# 16bit_EPROM.net
KiCad netlist of a schematic drawn in EAGLE
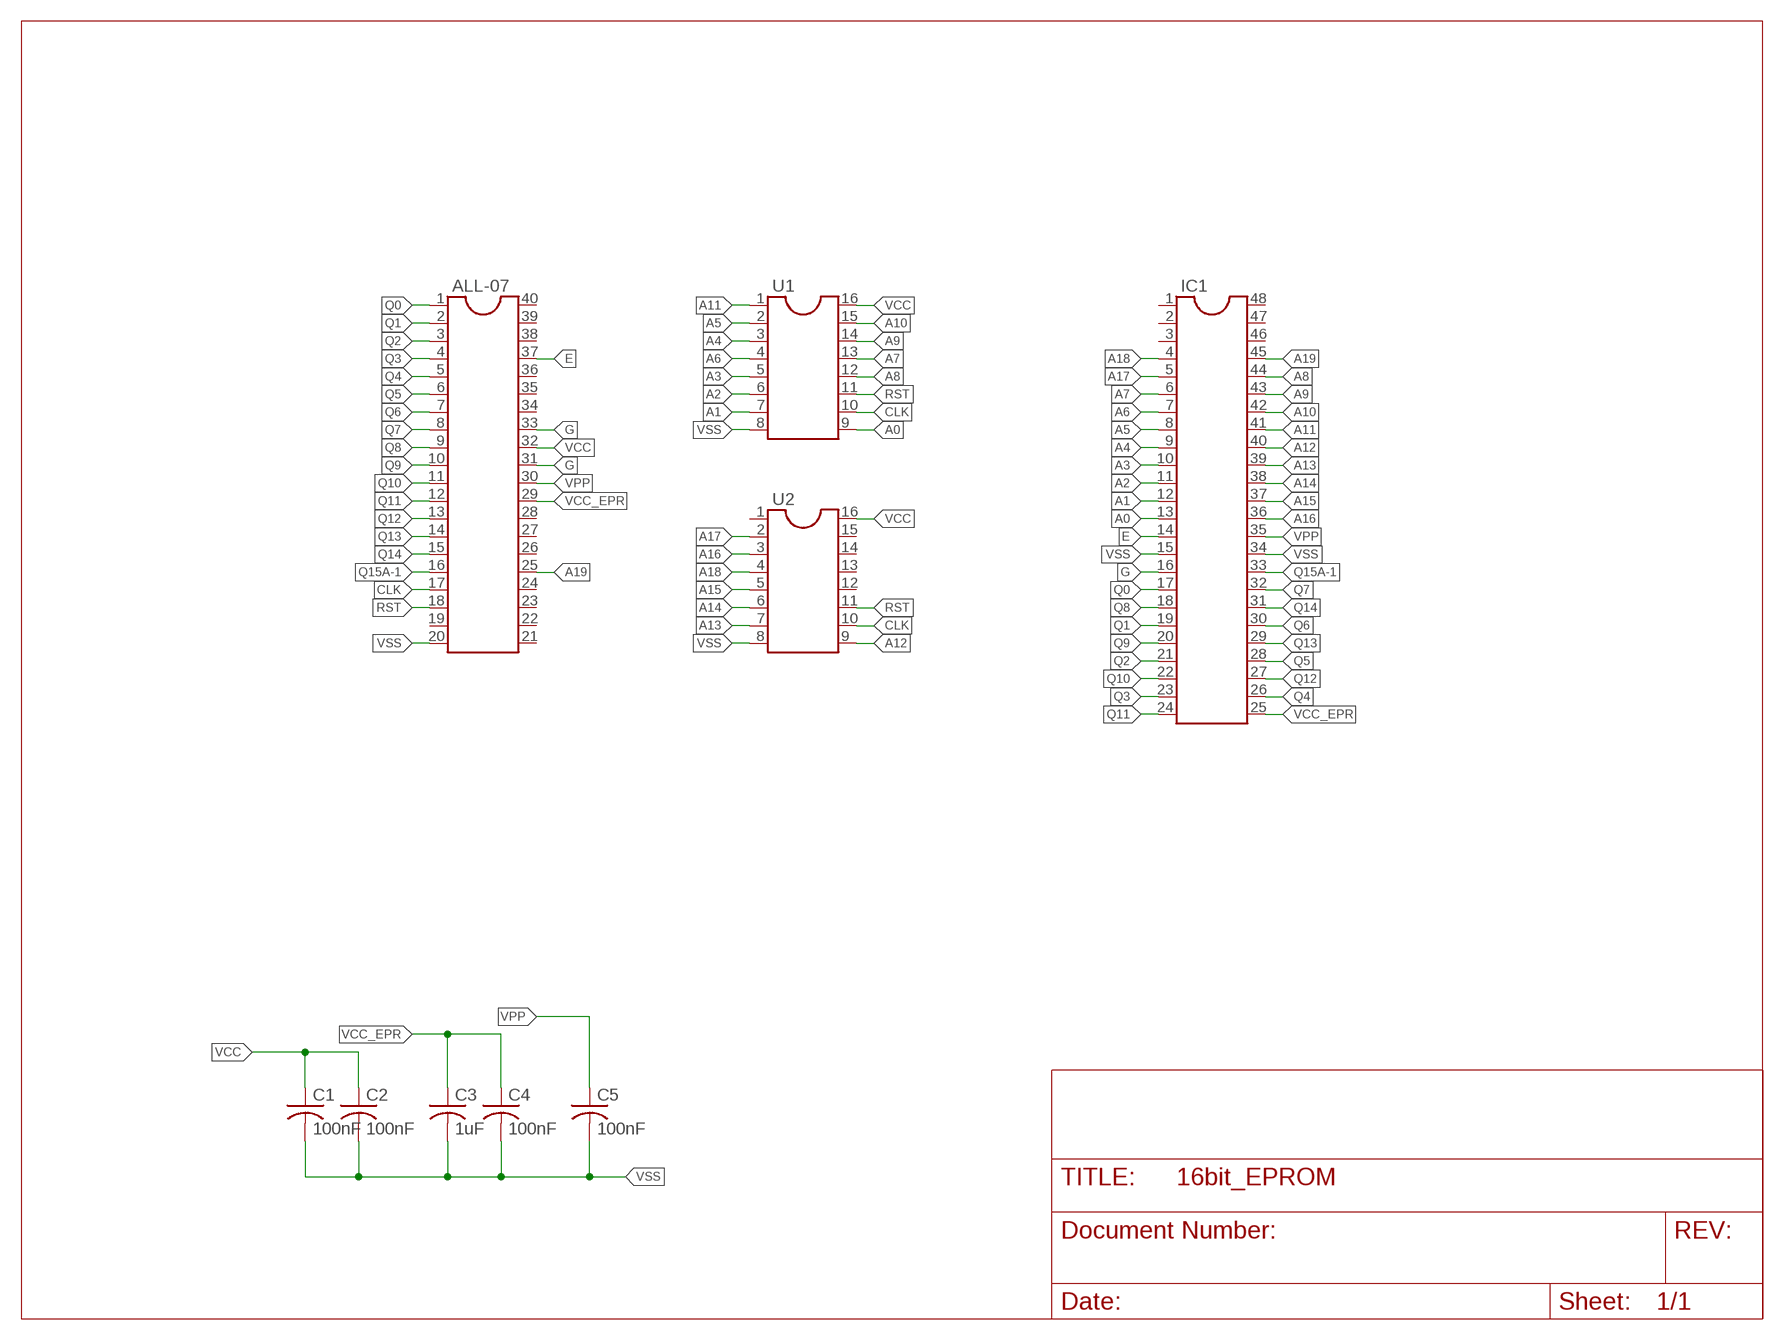
[diagram p0: schematic, sheet 1]

(export (version "E")
  (design (tool "Eeschema 10.0.6"))
  (components
    (comp (ref "ALL-07")
      (value "DIL40")
      (footprint "eagle-import:DIL40")
      (libsource (lib "eagle-import") (part "DIL40"))
    )
    (comp (ref "C1")
      (value "100nF")
      (footprint "eagle-import:C050-025X075")
      (libsource (lib "eagle-import") (part "C-US050-025X075"))
    )
    (comp (ref "C2")
      (value "100nF")
      (footprint "eagle-import:C050-025X075")
      (libsource (lib "eagle-import") (part "C-US050-025X075"))
    )
    (comp (ref "C3")
      (value "1uF")
      (footprint "eagle-import:C050-025X075")
      (libsource (lib "eagle-import") (part "C-US050-025X075"))
    )
    (comp (ref "C4")
      (value "100nF")
      (footprint "eagle-import:C050-025X075")
      (libsource (lib "eagle-import") (part "C-US050-025X075"))
    )
    (comp (ref "C5")
      (value "100nF")
      (footprint "eagle-import:C050-025X075")
      (libsource (lib "eagle-import") (part "C-US050-025X075"))
    )
    (comp (ref "IC1")
      (value "DIL48")
      (footprint "eagle-import:DIL48")
      (libsource (lib "eagle-import") (part "DIL48"))
    )
    (comp (ref "U1")
      (value "DIL16")
      (footprint "eagle-import:DIL16")
      (libsource (lib "eagle-import") (part "DIL16"))
    )
    (comp (ref "U2")
      (value "DIL16")
      (footprint "eagle-import:DIL16")
      (libsource (lib "eagle-import") (part "DIL16"))
    )
  )
  (nets
    (net (code "1") (name "A0") (class "Default")
      (node (ref "IC1") (pin "13") (pinfunction "13_13") (pintype "passive"))
      (node (ref "U1") (pin "9") (pinfunction "9_9") (pintype "passive"))
    )
    (net (code "2") (name "A1") (class "Default")
      (node (ref "IC1") (pin "12") (pinfunction "12_12") (pintype "passive"))
      (node (ref "U1") (pin "7") (pinfunction "7_7") (pintype "passive"))
    )
    (net (code "3") (name "A2") (class "Default")
      (node (ref "IC1") (pin "11") (pinfunction "11_11") (pintype "passive"))
      (node (ref "U1") (pin "6") (pinfunction "6_6") (pintype "passive"))
    )
    (net (code "4") (name "A3") (class "Default")
      (node (ref "IC1") (pin "10") (pinfunction "10_10") (pintype "passive"))
      (node (ref "U1") (pin "5") (pinfunction "5_5") (pintype "passive"))
    )
    (net (code "5") (name "A4") (class "Default")
      (node (ref "IC1") (pin "9") (pinfunction "9_9") (pintype "passive"))
      (node (ref "U1") (pin "3") (pinfunction "3_3") (pintype "passive"))
    )
    (net (code "6") (name "A5") (class "Default")
      (node (ref "IC1") (pin "8") (pinfunction "8_8") (pintype "passive"))
      (node (ref "U1") (pin "2") (pinfunction "2_2") (pintype "passive"))
    )
    (net (code "7") (name "A6") (class "Default")
      (node (ref "IC1") (pin "7") (pinfunction "7_7") (pintype "passive"))
      (node (ref "U1") (pin "4") (pinfunction "4_4") (pintype "passive"))
    )
    (net (code "8") (name "A7") (class "Default")
      (node (ref "IC1") (pin "6") (pinfunction "6_6") (pintype "passive"))
      (node (ref "U1") (pin "13") (pinfunction "13_13") (pintype "passive"))
    )
    (net (code "9") (name "A8") (class "Default")
      (node (ref "IC1") (pin "44") (pinfunction "44_44") (pintype "passive"))
      (node (ref "U1") (pin "12") (pinfunction "12_12") (pintype "passive"))
    )
    (net (code "10") (name "A9") (class "Default")
      (node (ref "IC1") (pin "43") (pinfunction "43_43") (pintype "passive"))
      (node (ref "U1") (pin "14") (pinfunction "14_14") (pintype "passive"))
    )
    (net (code "11") (name "A10") (class "Default")
      (node (ref "IC1") (pin "42") (pinfunction "42_42") (pintype "passive"))
      (node (ref "U1") (pin "15") (pinfunction "15_15") (pintype "passive"))
    )
    (net (code "12") (name "A11") (class "Default")
      (node (ref "IC1") (pin "41") (pinfunction "41_41") (pintype "passive"))
      (node (ref "U1") (pin "1") (pinfunction "1_1") (pintype "passive"))
    )
    (net (code "13") (name "A12") (class "Default")
      (node (ref "IC1") (pin "40") (pinfunction "40_40") (pintype "passive"))
      (node (ref "U2") (pin "9") (pinfunction "9_9") (pintype "passive"))
    )
    (net (code "14") (name "A13") (class "Default")
      (node (ref "IC1") (pin "39") (pinfunction "39_39") (pintype "passive"))
      (node (ref "U2") (pin "7") (pinfunction "7_7") (pintype "passive"))
    )
    (net (code "15") (name "A14") (class "Default")
      (node (ref "IC1") (pin "38") (pinfunction "38_38") (pintype "passive"))
      (node (ref "U2") (pin "6") (pinfunction "6_6") (pintype "passive"))
    )
    (net (code "16") (name "A15") (class "Default")
      (node (ref "IC1") (pin "37") (pinfunction "37_37") (pintype "passive"))
      (node (ref "U2") (pin "5") (pinfunction "5_5") (pintype "passive"))
    )
    (net (code "17") (name "A16") (class "Default")
      (node (ref "IC1") (pin "36") (pinfunction "36_36") (pintype "passive"))
      (node (ref "U2") (pin "3") (pinfunction "3_3") (pintype "passive"))
    )
    (net (code "18") (name "A17") (class "Default")
      (node (ref "IC1") (pin "5") (pinfunction "5_5") (pintype "passive"))
      (node (ref "U2") (pin "2") (pinfunction "2_2") (pintype "passive"))
    )
    (net (code "19") (name "A18") (class "Default")
      (node (ref "IC1") (pin "4") (pinfunction "4_4") (pintype "passive"))
      (node (ref "U2") (pin "4") (pinfunction "4_4") (pintype "passive"))
    )
    (net (code "20") (name "A19") (class "Default")
      (node (ref "ALL-07") (pin "25") (pinfunction "25_25") (pintype "passive"))
      (node (ref "IC1") (pin "45") (pinfunction "45_45") (pintype "passive"))
    )
    (net (code "21") (name "CLK") (class "Default")
      (node (ref "ALL-07") (pin "17") (pinfunction "17_17") (pintype "passive"))
      (node (ref "U1") (pin "10") (pinfunction "10_10") (pintype "passive"))
      (node (ref "U2") (pin "10") (pinfunction "10_10") (pintype "passive"))
    )
    (net (code "22") (name "E") (class "Default")
      (node (ref "ALL-07") (pin "37") (pinfunction "37_37") (pintype "passive"))
      (node (ref "IC1") (pin "14") (pinfunction "14_14") (pintype "passive"))
    )
    (net (code "23") (name "G") (class "Default")
      (node (ref "ALL-07") (pin "31") (pinfunction "31_31") (pintype "passive"))
      (node (ref "ALL-07") (pin "33") (pinfunction "33_33") (pintype "passive"))
      (node (ref "IC1") (pin "16") (pinfunction "16_16") (pintype "passive"))
    )
    (net (code "24") (name "Q0") (class "Default")
      (node (ref "ALL-07") (pin "1") (pinfunction "1_1") (pintype "passive"))
      (node (ref "IC1") (pin "17") (pinfunction "17_17") (pintype "passive"))
    )
    (net (code "25") (name "Q1") (class "Default")
      (node (ref "ALL-07") (pin "2") (pinfunction "2_2") (pintype "passive"))
      (node (ref "IC1") (pin "19") (pinfunction "19_19") (pintype "passive"))
    )
    (net (code "26") (name "Q2") (class "Default")
      (node (ref "ALL-07") (pin "3") (pinfunction "3_3") (pintype "passive"))
      (node (ref "IC1") (pin "21") (pinfunction "21_21") (pintype "passive"))
    )
    (net (code "27") (name "Q3") (class "Default")
      (node (ref "ALL-07") (pin "4") (pinfunction "4_4") (pintype "passive"))
      (node (ref "IC1") (pin "23") (pinfunction "23_23") (pintype "passive"))
    )
    (net (code "28") (name "Q4") (class "Default")
      (node (ref "ALL-07") (pin "5") (pinfunction "5_5") (pintype "passive"))
      (node (ref "IC1") (pin "26") (pinfunction "26_26") (pintype "passive"))
    )
    (net (code "29") (name "Q5") (class "Default")
      (node (ref "ALL-07") (pin "6") (pinfunction "6_6") (pintype "passive"))
      (node (ref "IC1") (pin "28") (pinfunction "28_28") (pintype "passive"))
    )
    (net (code "30") (name "Q6") (class "Default")
      (node (ref "ALL-07") (pin "7") (pinfunction "7_7") (pintype "passive"))
      (node (ref "IC1") (pin "30") (pinfunction "30_30") (pintype "passive"))
    )
    (net (code "31") (name "Q7") (class "Default")
      (node (ref "ALL-07") (pin "8") (pinfunction "8_8") (pintype "passive"))
      (node (ref "IC1") (pin "32") (pinfunction "32_32") (pintype "passive"))
    )
    (net (code "32") (name "Q8") (class "Default")
      (node (ref "ALL-07") (pin "9") (pinfunction "9_9") (pintype "passive"))
      (node (ref "IC1") (pin "18") (pinfunction "18_18") (pintype "passive"))
    )
    (net (code "33") (name "Q9") (class "Default")
      (node (ref "ALL-07") (pin "10") (pinfunction "10_10") (pintype "passive"))
      (node (ref "IC1") (pin "20") (pinfunction "20_20") (pintype "passive"))
    )
    (net (code "34") (name "Q10") (class "Default")
      (node (ref "ALL-07") (pin "11") (pinfunction "11_11") (pintype "passive"))
      (node (ref "IC1") (pin "22") (pinfunction "22_22") (pintype "passive"))
    )
    (net (code "35") (name "Q11") (class "Default")
      (node (ref "ALL-07") (pin "12") (pinfunction "12_12") (pintype "passive"))
      (node (ref "IC1") (pin "24") (pinfunction "24_24") (pintype "passive"))
    )
    (net (code "36") (name "Q12") (class "Default")
      (node (ref "ALL-07") (pin "13") (pinfunction "13_13") (pintype "passive"))
      (node (ref "IC1") (pin "27") (pinfunction "27_27") (pintype "passive"))
    )
    (net (code "37") (name "Q13") (class "Default")
      (node (ref "ALL-07") (pin "14") (pinfunction "14_14") (pintype "passive"))
      (node (ref "IC1") (pin "29") (pinfunction "29_29") (pintype "passive"))
    )
    (net (code "38") (name "Q14") (class "Default")
      (node (ref "ALL-07") (pin "15") (pinfunction "15_15") (pintype "passive"))
      (node (ref "IC1") (pin "31") (pinfunction "31_31") (pintype "passive"))
    )
    (net (code "39") (name "Q15A-1") (class "Default")
      (node (ref "ALL-07") (pin "16") (pinfunction "16_16") (pintype "passive"))
      (node (ref "IC1") (pin "33") (pinfunction "33_33") (pintype "passive"))
    )
    (net (code "40") (name "RST") (class "Default")
      (node (ref "ALL-07") (pin "18") (pinfunction "18_18") (pintype "passive"))
      (node (ref "U1") (pin "11") (pinfunction "11_11") (pintype "passive"))
      (node (ref "U2") (pin "11") (pinfunction "11_11") (pintype "passive"))
    )
    (net (code "41") (name "VCC") (class "Default")
      (node (ref "ALL-07") (pin "32") (pinfunction "32_32") (pintype "passive"))
      (node (ref "C1") (pin "1") (pinfunction "1_1") (pintype "passive"))
      (node (ref "C2") (pin "1") (pinfunction "1_1") (pintype "passive"))
      (node (ref "U1") (pin "16") (pinfunction "16_16") (pintype "passive"))
      (node (ref "U2") (pin "16") (pinfunction "16_16") (pintype "passive"))
    )
    (net (code "42") (name "VCC_EPR") (class "Default")
      (node (ref "ALL-07") (pin "29") (pinfunction "29_29") (pintype "passive"))
      (node (ref "C3") (pin "1") (pinfunction "1_1") (pintype "passive"))
      (node (ref "C4") (pin "1") (pinfunction "1_1") (pintype "passive"))
      (node (ref "IC1") (pin "25") (pinfunction "25_25") (pintype "passive"))
    )
    (net (code "43") (name "VPP") (class "Default")
      (node (ref "ALL-07") (pin "30") (pinfunction "30_30") (pintype "passive"))
      (node (ref "C5") (pin "1") (pinfunction "1_1") (pintype "passive"))
      (node (ref "IC1") (pin "35") (pinfunction "35_35") (pintype "passive"))
    )
    (net (code "44") (name "VSS") (class "Default")
      (node (ref "ALL-07") (pin "20") (pinfunction "20_20") (pintype "passive"))
      (node (ref "C1") (pin "2") (pinfunction "2_2") (pintype "passive"))
      (node (ref "C2") (pin "2") (pinfunction "2_2") (pintype "passive"))
      (node (ref "C3") (pin "2") (pinfunction "2_2") (pintype "passive"))
      (node (ref "C4") (pin "2") (pinfunction "2_2") (pintype "passive"))
      (node (ref "C5") (pin "2") (pinfunction "2_2") (pintype "passive"))
      (node (ref "IC1") (pin "15") (pinfunction "15_15") (pintype "passive"))
      (node (ref "IC1") (pin "34") (pinfunction "34_34") (pintype "passive"))
      (node (ref "U1") (pin "8") (pinfunction "8_8") (pintype "passive"))
      (node (ref "U2") (pin "8") (pinfunction "8_8") (pintype "passive"))
    )
    (net (code "45") (name "unconnected-(ALL-07-Pad19)") (class "Default")
      (node (ref "ALL-07") (pin "19") (pinfunction "19_19") (pintype "passive"))
    )
    (net (code "46") (name "unconnected-(ALL-07-Pad21)") (class "Default")
      (node (ref "ALL-07") (pin "21") (pinfunction "21_21") (pintype "passive"))
    )
    (net (code "47") (name "unconnected-(ALL-07-Pad22)") (class "Default")
      (node (ref "ALL-07") (pin "22") (pinfunction "22_22") (pintype "passive"))
    )
    (net (code "48") (name "unconnected-(ALL-07-Pad23)") (class "Default")
      (node (ref "ALL-07") (pin "23") (pinfunction "23_23") (pintype "passive"))
    )
    (net (code "49") (name "unconnected-(ALL-07-Pad24)") (class "Default")
      (node (ref "ALL-07") (pin "24") (pinfunction "24_24") (pintype "passive"))
    )
    (net (code "50") (name "unconnected-(ALL-07-Pad26)") (class "Default")
      (node (ref "ALL-07") (pin "26") (pinfunction "26_26") (pintype "passive"))
    )
    (net (code "51") (name "unconnected-(ALL-07-Pad27)") (class "Default")
      (node (ref "ALL-07") (pin "27") (pinfunction "27_27") (pintype "passive"))
    )
    (net (code "52") (name "unconnected-(ALL-07-Pad28)") (class "Default")
      (node (ref "ALL-07") (pin "28") (pinfunction "28_28") (pintype "passive"))
    )
    (net (code "53") (name "unconnected-(ALL-07-Pad34)") (class "Default")
      (node (ref "ALL-07") (pin "34") (pinfunction "34_34") (pintype "passive"))
    )
    (net (code "54") (name "unconnected-(ALL-07-Pad35)") (class "Default")
      (node (ref "ALL-07") (pin "35") (pinfunction "35_35") (pintype "passive"))
    )
    (net (code "55") (name "unconnected-(ALL-07-Pad36)") (class "Default")
      (node (ref "ALL-07") (pin "36") (pinfunction "36_36") (pintype "passive"))
    )
    (net (code "56") (name "unconnected-(ALL-07-Pad38)") (class "Default")
      (node (ref "ALL-07") (pin "38") (pinfunction "38_38") (pintype "passive"))
    )
    (net (code "57") (name "unconnected-(ALL-07-Pad39)") (class "Default")
      (node (ref "ALL-07") (pin "39") (pinfunction "39_39") (pintype "passive"))
    )
    (net (code "58") (name "unconnected-(ALL-07-Pad40)") (class "Default")
      (node (ref "ALL-07") (pin "40") (pinfunction "40_40") (pintype "passive"))
    )
    (net (code "59") (name "unconnected-(IC1-Pad1)") (class "Default")
      (node (ref "IC1") (pin "1") (pinfunction "1_1") (pintype "passive"))
    )
    (net (code "60") (name "unconnected-(IC1-Pad2)") (class "Default")
      (node (ref "IC1") (pin "2") (pinfunction "2_2") (pintype "passive"))
    )
    (net (code "61") (name "unconnected-(IC1-Pad3)") (class "Default")
      (node (ref "IC1") (pin "3") (pinfunction "3_3") (pintype "passive"))
    )
    (net (code "62") (name "unconnected-(IC1-Pad46)") (class "Default")
      (node (ref "IC1") (pin "46") (pinfunction "46_46") (pintype "passive"))
    )
    (net (code "63") (name "unconnected-(IC1-Pad47)") (class "Default")
      (node (ref "IC1") (pin "47") (pinfunction "47_47") (pintype "passive"))
    )
    (net (code "64") (name "unconnected-(IC1-Pad48)") (class "Default")
      (node (ref "IC1") (pin "48") (pinfunction "48_48") (pintype "passive"))
    )
    (net (code "65") (name "unconnected-(U2-Pad1)") (class "Default")
      (node (ref "U2") (pin "1") (pinfunction "1_1") (pintype "passive"))
    )
    (net (code "66") (name "unconnected-(U2-Pad12)") (class "Default")
      (node (ref "U2") (pin "12") (pinfunction "12_12") (pintype "passive"))
    )
    (net (code "67") (name "unconnected-(U2-Pad13)") (class "Default")
      (node (ref "U2") (pin "13") (pinfunction "13_13") (pintype "passive"))
    )
    (net (code "68") (name "unconnected-(U2-Pad14)") (class "Default")
      (node (ref "U2") (pin "14") (pinfunction "14_14") (pintype "passive"))
    )
    (net (code "69") (name "unconnected-(U2-Pad15)") (class "Default")
      (node (ref "U2") (pin "15") (pinfunction "15_15") (pintype "passive"))
    )
  )
)
